# VCO_eagle.net
KiCad netlist of a schematic drawn in EAGLE
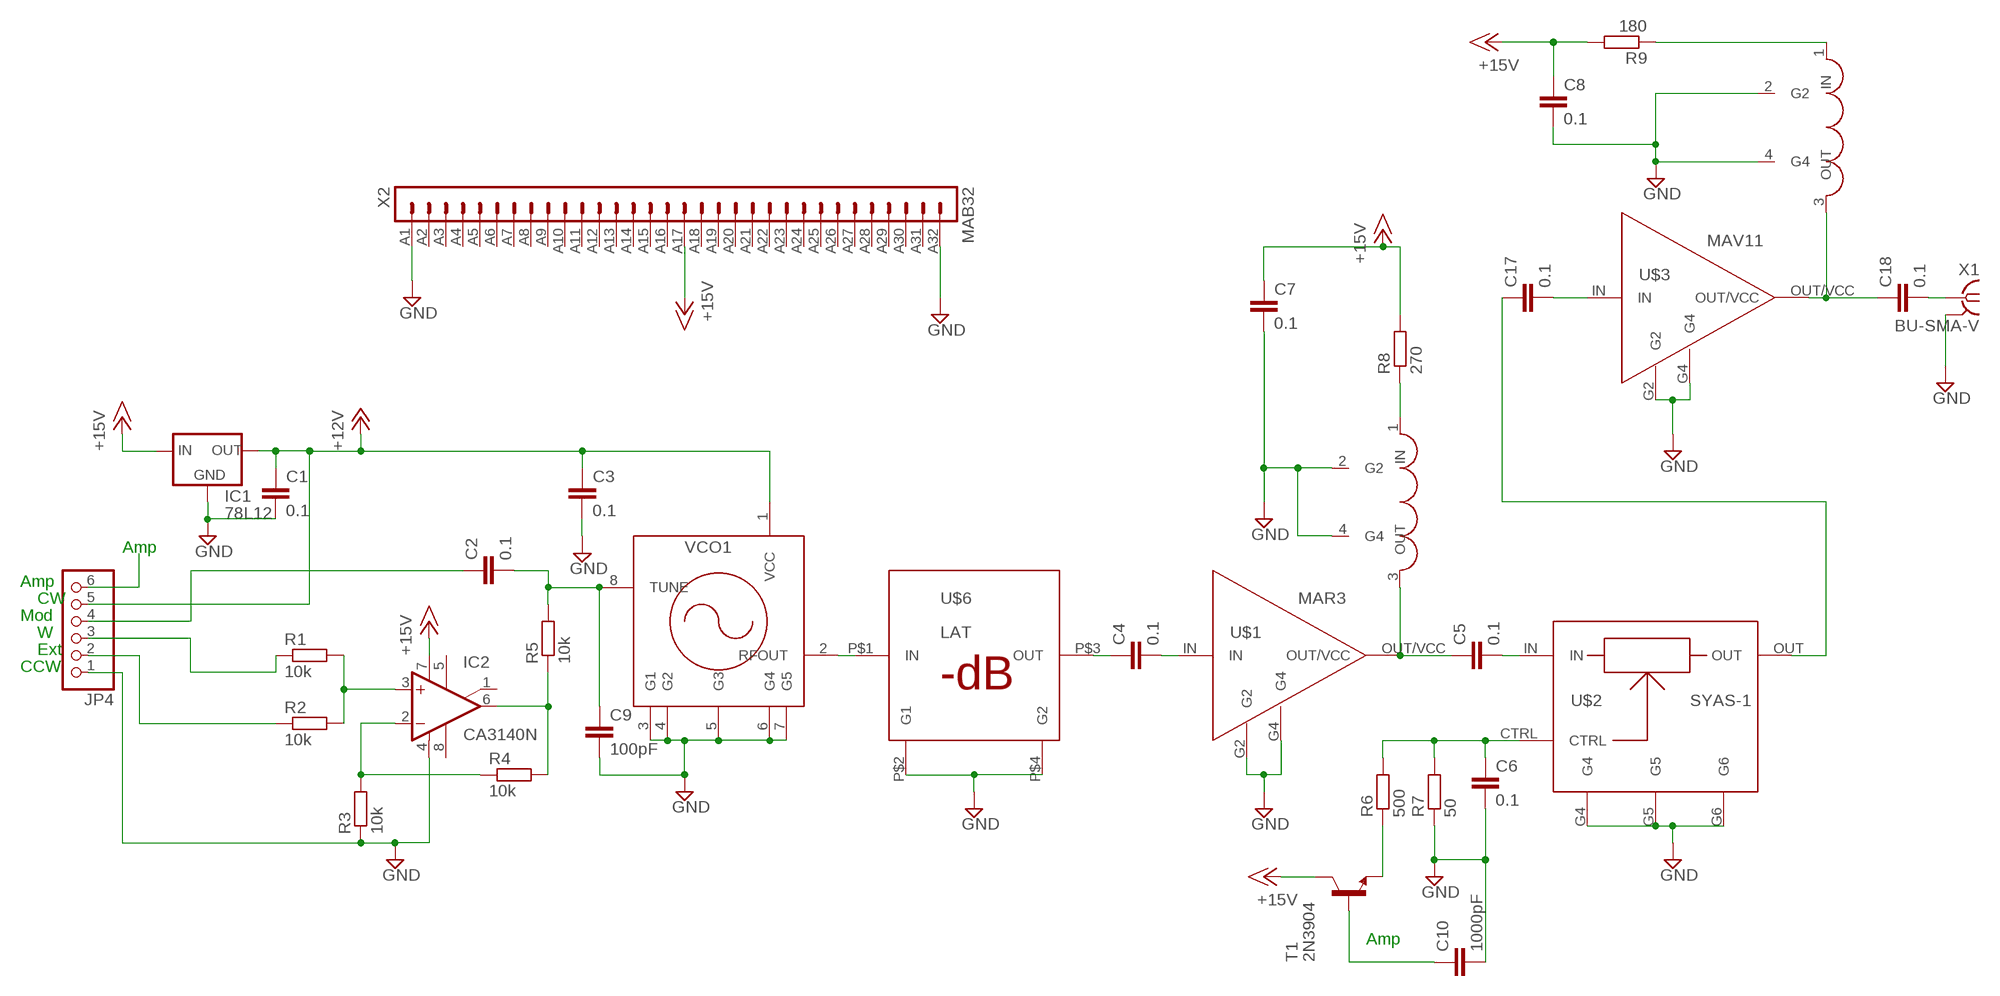
[diagram p0: schematic, sheet 1]

(export (version "E")
  (design (tool "Eeschema 10.0.6"))
  (components
    (comp (ref "C1")
      (value "0.1")
      (footprint "eagle-import:C1210")
      (libsource (lib "eagle-import") (part "C-EUC1210"))
    )
    (comp (ref "C2")
      (value "0.1")
      (footprint "eagle-import:C1210")
      (libsource (lib "eagle-import") (part "C-EUC1210"))
    )
    (comp (ref "C3")
      (value "0.1")
      (footprint "eagle-import:C1210")
      (libsource (lib "eagle-import") (part "C-EUC1210"))
    )
    (comp (ref "C4")
      (value "0.1")
      (footprint "eagle-import:C1210")
      (libsource (lib "eagle-import") (part "C-EUC1210"))
    )
    (comp (ref "C5")
      (value "0.1")
      (footprint "eagle-import:C1210")
      (libsource (lib "eagle-import") (part "C-EUC1210"))
    )
    (comp (ref "C6")
      (value "0.1")
      (footprint "eagle-import:C1210")
      (libsource (lib "eagle-import") (part "C-EUC1210"))
    )
    (comp (ref "C7")
      (value "0.1")
      (footprint "eagle-import:C1210")
      (libsource (lib "eagle-import") (part "C-EUC1210"))
    )
    (comp (ref "C8")
      (value "0.1")
      (footprint "eagle-import:C1210")
      (libsource (lib "eagle-import") (part "C-EUC1210"))
    )
    (comp (ref "C9")
      (value "100pF")
      (footprint "eagle-import:C0805")
      (libsource (lib "eagle-import") (part "C-EUC0805"))
    )
    (comp (ref "C10")
      (value "1000pF")
      (footprint "eagle-import:C0805")
      (libsource (lib "eagle-import") (part "C-EUC0805"))
    )
    (comp (ref "C17")
      (value "0.1")
      (footprint "eagle-import:C1206")
      (libsource (lib "eagle-import") (part "C-EUC1206"))
    )
    (comp (ref "C18")
      (value "0.1")
      (footprint "eagle-import:C1206")
      (libsource (lib "eagle-import") (part "C-EUC1206"))
    )
    (comp (ref "IC1")
      (value "78L12")
      (footprint "eagle-import:78LXX")
      (libsource (lib "eagle-import") (part "78LXX"))
    )
    (comp (ref "IC2")
      (value "CA3140N")
      (footprint "eagle-import:DIL08")
      (libsource (lib "eagle-import") (part "CA3140N"))
    )
    (comp (ref "JP4")
      (value "PINHD-1X6")
      (footprint "eagle-import:1X06")
      (libsource (lib "eagle-import") (part "PINHD-1X6"))
    )
    (comp (ref "R1")
      (value "10k")
      (footprint "eagle-import:0204_7")
      (libsource (lib "eagle-import") (part "R-EU_0204/7"))
    )
    (comp (ref "R2")
      (value "10k")
      (footprint "eagle-import:0204_7")
      (libsource (lib "eagle-import") (part "R-EU_0204/7"))
    )
    (comp (ref "R3")
      (value "10k")
      (footprint "eagle-import:0204_7")
      (libsource (lib "eagle-import") (part "R-EU_0204/7"))
    )
    (comp (ref "R4")
      (value "10k")
      (footprint "eagle-import:0204_7")
      (libsource (lib "eagle-import") (part "R-EU_0204/7"))
    )
    (comp (ref "R5")
      (value "10k")
      (footprint "eagle-import:0204_7")
      (libsource (lib "eagle-import") (part "R-EU_0204/7"))
    )
    (comp (ref "R6")
      (value "500")
      (footprint "eagle-import:0204_7")
      (libsource (lib "eagle-import") (part "R-EU_0204/7"))
    )
    (comp (ref "R7")
      (value "50")
      (footprint "eagle-import:0204_7")
      (libsource (lib "eagle-import") (part "R-EU_0204/7"))
    )
    (comp (ref "R8")
      (value "270")
      (footprint "eagle-import:R1206")
      (libsource (lib "eagle-import") (part "R-EU_R1206"))
    )
    (comp (ref "R9")
      (value "180")
      (footprint "eagle-import:R1206")
      (libsource (lib "eagle-import") (part "R-EU_R1206"))
    )
    (comp (ref "T1")
      (value "2N3904")
      (footprint "eagle-import:TO92")
      (libsource (lib "eagle-import") (part "2N3904"))
    )
    (comp (ref "U$1")
      (value "MAR3")
      (footprint "eagle-import:MAR")
      (libsource (lib "eagle-import") (part "MAR3"))
    )
    (comp (ref "U$2")
      (value "SYAS-1")
      (footprint "eagle-import:TTT166")
      (libsource (lib "eagle-import") (part "SYAS-1"))
    )
    (comp (ref "U$3")
      (value "MAV11")
      (footprint "eagle-import:MAR")
      (libsource (lib "eagle-import") (part "MAV11"))
    )
    (comp (ref "U$4")
      (value "TCCH-80")
      (footprint "eagle-import:PL-147")
      (libsource (lib "eagle-import") (part "TCCH-80"))
    )
    (comp (ref "U$5")
      (value "TCCH-80")
      (footprint "eagle-import:PL-147")
      (libsource (lib "eagle-import") (part "TCCH-80"))
    )
    (comp (ref "U$6")
      (value "LAT")
      (footprint "eagle-import:MMM168")
      (libsource (lib "eagle-import") (part "LAT"))
    )
    (comp (ref "VCO1")
      (value "POS")
      (footprint "eagle-import:A01")
      (libsource (lib "eagle-import") (part "POS"))
    )
    (comp (ref "X1")
      (value "BU-SMA-V")
      (footprint "eagle-import:BU-SMA-V")
      (libsource (lib "eagle-import") (part "BU-SMA-V"))
    )
    (comp (ref "X2")
      (value "MAB32")
      (footprint "eagle-import:MAB32")
      (libsource (lib "eagle-import") (part "MAB32"))
    )
  )
  (nets
    (net (code "1") (name "+12V") (class "Default")
      (node (ref "C1") (pin "1") (pinfunction "1_1") (pintype "passive"))
      (node (ref "C3") (pin "1") (pinfunction "1_1") (pintype "passive"))
      (node (ref "IC1") (pin "OUT") (pinfunction "OUT_OUT") (pintype "passive"))
      (node (ref "JP4") (pin "5") (pinfunction "5_5") (pintype "passive"))
      (node (ref "VCO1") (pin "1") (pinfunction "VCC_1") (pintype "input"))
    )
    (net (code "2") (name "+15V") (class "Default")
      (node (ref "C7") (pin "1") (pinfunction "1_1") (pintype "passive"))
      (node (ref "C8") (pin "1") (pinfunction "1_1") (pintype "passive"))
      (node (ref "IC1") (pin "IN") (pinfunction "IN_IN") (pintype "input"))
      (node (ref "IC2") (pin "7") (pinfunction "V+_7") (pintype "power_in"))
      (node (ref "R8") (pin "2") (pinfunction "2_2") (pintype "passive"))
      (node (ref "R9") (pin "2") (pinfunction "2_2") (pintype "passive"))
      (node (ref "T1") (pin "1") (pinfunction "C_1") (pintype "passive"))
      (node (ref "X2") (pin "A17") (pinfunction "17_A17") (pintype "passive"))
    )
    (net (code "3") (name "/AMP") (class "Default")
      (node (ref "C10") (pin "1") (pinfunction "1_1") (pintype "passive"))
      (node (ref "JP4") (pin "6") (pinfunction "6_6") (pintype "passive"))
      (node (ref "T1") (pin "2") (pinfunction "B_2") (pintype "passive"))
    )
    (net (code "4") (name "GND") (class "Default")
      (node (ref "C1") (pin "2") (pinfunction "2_2") (pintype "passive"))
      (node (ref "C10") (pin "2") (pinfunction "2_2") (pintype "passive"))
      (node (ref "C3") (pin "2") (pinfunction "2_2") (pintype "passive"))
      (node (ref "C6") (pin "2") (pinfunction "2_2") (pintype "passive"))
      (node (ref "C7") (pin "2") (pinfunction "2_2") (pintype "passive"))
      (node (ref "C8") (pin "2") (pinfunction "2_2") (pintype "passive"))
      (node (ref "C9") (pin "2") (pinfunction "2_2") (pintype "passive"))
      (node (ref "IC1") (pin "GND") (pinfunction "GND_GND") (pintype "input"))
      (node (ref "IC2") (pin "4") (pinfunction "V-_4") (pintype "power_in"))
      (node (ref "JP4") (pin "1") (pinfunction "1_1") (pintype "passive"))
      (node (ref "R3") (pin "1") (pinfunction "1_1") (pintype "passive"))
      (node (ref "R7") (pin "1") (pinfunction "1_1") (pintype "passive"))
      (node (ref "U$1") (pin "G2") (pinfunction "G2_G2") (pintype "power_in"))
      (node (ref "U$1") (pin "G4") (pinfunction "G4_G4") (pintype "power_in"))
      (node (ref "U$2") (pin "G4") (pinfunction "G4_G4") (pintype "power_in"))
      (node (ref "U$2") (pin "G5") (pinfunction "G5_G5") (pintype "power_in"))
      (node (ref "U$2") (pin "G6") (pinfunction "G6_G6") (pintype "power_in"))
      (node (ref "U$3") (pin "G2") (pinfunction "G2_G2") (pintype "power_in"))
      (node (ref "U$3") (pin "G4") (pinfunction "G4_G4") (pintype "power_in"))
      (node (ref "U$4") (pin "2") (pinfunction "G2_2") (pintype "power_in"))
      (node (ref "U$4") (pin "4") (pinfunction "G4_4") (pintype "power_in"))
      (node (ref "U$5") (pin "2") (pinfunction "G2_2") (pintype "power_in"))
      (node (ref "U$5") (pin "4") (pinfunction "G4_4") (pintype "power_in"))
      (node (ref "U$6") (pin "P$2") (pinfunction "G1_P$2") (pintype "power_in"))
      (node (ref "U$6") (pin "P$4") (pinfunction "G2_P$4") (pintype "power_in"))
      (node (ref "VCO1") (pin "3") (pinfunction "G1_3") (pintype "power_in"))
      (node (ref "VCO1") (pin "4") (pinfunction "G2_4") (pintype "power_in"))
      (node (ref "VCO1") (pin "5") (pinfunction "G3_5") (pintype "power_in"))
      (node (ref "VCO1") (pin "6") (pinfunction "G4_6") (pintype "power_in"))
      (node (ref "VCO1") (pin "7") (pinfunction "G5_7") (pintype "power_in"))
      (node (ref "X1") (pin "2") (pinfunction "GND_2") (pintype "power_in"))
      (node (ref "X2") (pin "A1") (pinfunction "1_A1") (pintype "passive"))
      (node (ref "X2") (pin "A32") (pinfunction "32_A32") (pintype "passive"))
    )
    (net (code "5") (name "Net-(C2-Pad1)") (class "Default")
      (node (ref "C2") (pin "1") (pinfunction "1_1") (pintype "passive"))
      (node (ref "JP4") (pin "4") (pinfunction "4_4") (pintype "passive"))
    )
    (net (code "6") (name "Net-(C4-Pad2)") (class "Default")
      (node (ref "C4") (pin "2") (pinfunction "2_2") (pintype "passive"))
      (node (ref "U$1") (pin "IN") (pinfunction "IN_IN") (pintype "input"))
    )
    (net (code "7") (name "Net-(C5-Pad2)") (class "Default")
      (node (ref "C5") (pin "2") (pinfunction "2_2") (pintype "passive"))
      (node (ref "U$2") (pin "IN") (pinfunction "IN_IN") (pintype "input"))
    )
    (net (code "8") (name "Net-(C6-Pad1)") (class "Default")
      (node (ref "C6") (pin "1") (pinfunction "1_1") (pintype "passive"))
      (node (ref "R6") (pin "2") (pinfunction "2_2") (pintype "passive"))
      (node (ref "R7") (pin "2") (pinfunction "2_2") (pintype "passive"))
      (node (ref "U$2") (pin "CTRL") (pinfunction "CTRL_CTRL") (pintype "input"))
    )
    (net (code "9") (name "Net-(C17-Pad1)") (class "Default")
      (node (ref "C17") (pin "1") (pinfunction "1_1") (pintype "passive"))
      (node (ref "U$2") (pin "OUT") (pinfunction "OUT_OUT") (pintype "output"))
    )
    (net (code "10") (name "Net-(C17-Pad2)") (class "Default")
      (node (ref "C17") (pin "2") (pinfunction "2_2") (pintype "passive"))
      (node (ref "U$3") (pin "IN") (pinfunction "IN_IN") (pintype "input"))
    )
    (net (code "11") (name "Net-(C18-Pad2)") (class "Default")
      (node (ref "C18") (pin "2") (pinfunction "2_2") (pintype "passive"))
      (node (ref "X1") (pin "1") (pinfunction "1_1") (pintype "passive"))
    )
    (net (code "12") (name "Net-(IC2-+IN)") (class "Default")
      (node (ref "IC2") (pin "3") (pinfunction "+IN_3") (pintype "input"))
      (node (ref "R1") (pin "2") (pinfunction "2_2") (pintype "passive"))
      (node (ref "R2") (pin "2") (pinfunction "2_2") (pintype "passive"))
    )
    (net (code "13") (name "Net-(IC2--IN)") (class "Default")
      (node (ref "IC2") (pin "2") (pinfunction "-IN_2") (pintype "input"))
      (node (ref "R3") (pin "2") (pinfunction "2_2") (pintype "passive"))
      (node (ref "R4") (pin "1") (pinfunction "1_1") (pintype "passive"))
    )
    (net (code "14") (name "Net-(IC2-OUT)") (class "Default")
      (node (ref "IC2") (pin "6") (pinfunction "OUT_6") (pintype "output"))
      (node (ref "R4") (pin "2") (pinfunction "2_2") (pintype "passive"))
      (node (ref "R5") (pin "1") (pinfunction "1_1") (pintype "passive"))
    )
    (net (code "15") (name "Net-(JP4-Pad2)") (class "Default")
      (node (ref "JP4") (pin "2") (pinfunction "2_2") (pintype "passive"))
      (node (ref "R2") (pin "1") (pinfunction "1_1") (pintype "passive"))
    )
    (net (code "16") (name "Net-(JP4-Pad3)") (class "Default")
      (node (ref "JP4") (pin "3") (pinfunction "3_3") (pintype "passive"))
      (node (ref "R1") (pin "1") (pinfunction "1_1") (pintype "passive"))
    )
    (net (code "17") (name "Net-(T1-E)") (class "Default")
      (node (ref "R6") (pin "1") (pinfunction "1_1") (pintype "passive"))
      (node (ref "T1") (pin "3") (pinfunction "E_3") (pintype "passive"))
    )
    (net (code "18") (name "Net-(U$4-IN)") (class "Default")
      (node (ref "R8") (pin "1") (pinfunction "1_1") (pintype "passive"))
      (node (ref "U$4") (pin "1") (pinfunction "IN_1") (pintype "input"))
    )
    (net (code "19") (name "Net-(U$4-OUT)") (class "Default")
      (node (ref "C5") (pin "1") (pinfunction "1_1") (pintype "passive"))
      (node (ref "U$1") (pin "OUT/VCC") (pinfunction "OUT/VCC_OUT/VCC") (pintype "bidirectional"))
      (node (ref "U$4") (pin "3") (pinfunction "OUT_3") (pintype "output"))
    )
    (net (code "20") (name "Net-(U$5-IN)") (class "Default")
      (node (ref "R9") (pin "1") (pinfunction "1_1") (pintype "passive"))
      (node (ref "U$5") (pin "1") (pinfunction "IN_1") (pintype "input"))
    )
    (net (code "21") (name "Net-(U$5-OUT)") (class "Default")
      (node (ref "C18") (pin "1") (pinfunction "1_1") (pintype "passive"))
      (node (ref "U$3") (pin "OUT/VCC") (pinfunction "OUT/VCC_OUT/VCC") (pintype "bidirectional"))
      (node (ref "U$5") (pin "3") (pinfunction "OUT_3") (pintype "output"))
    )
    (net (code "22") (name "Net-(U$6-IN)") (class "Default")
      (node (ref "U$6") (pin "P$1") (pinfunction "IN_P$1") (pintype "input"))
      (node (ref "VCO1") (pin "2") (pinfunction "RFOUT_2") (pintype "output"))
    )
    (net (code "23") (name "Net-(U$6-OUT)") (class "Default")
      (node (ref "C4") (pin "1") (pinfunction "1_1") (pintype "passive"))
      (node (ref "U$6") (pin "P$3") (pinfunction "OUT_P$3") (pintype "output"))
    )
    (net (code "24") (name "Net-(VCO1-TUNE)") (class "Default")
      (node (ref "C2") (pin "2") (pinfunction "2_2") (pintype "passive"))
      (node (ref "C9") (pin "1") (pinfunction "1_1") (pintype "passive"))
      (node (ref "R5") (pin "2") (pinfunction "2_2") (pintype "passive"))
      (node (ref "VCO1") (pin "8") (pinfunction "TUNE_8") (pintype "input"))
    )
    (net (code "25") (name "unconnected-(IC2-CMP-Pad8)") (class "Default")
      (node (ref "IC2") (pin "8") (pinfunction "CMP_8") (pintype "passive"))
    )
    (net (code "26") (name "unconnected-(IC2-ON-Pad5)") (class "Default")
      (node (ref "IC2") (pin "5") (pinfunction "ON_5") (pintype "passive"))
    )
    (net (code "27") (name "unconnected-(IC2-ON{slash}CMP-Pad1)") (class "Default")
      (node (ref "IC2") (pin "1") (pinfunction "ON/CMP_1") (pintype "passive"))
    )
    (net (code "28") (name "unconnected-(X2-2-PadA2)") (class "Default")
      (node (ref "X2") (pin "A2") (pinfunction "2_A2") (pintype "passive"))
    )
    (net (code "29") (name "unconnected-(X2-3-PadA3)") (class "Default")
      (node (ref "X2") (pin "A3") (pinfunction "3_A3") (pintype "passive"))
    )
    (net (code "30") (name "unconnected-(X2-4-PadA4)") (class "Default")
      (node (ref "X2") (pin "A4") (pinfunction "4_A4") (pintype "passive"))
    )
    (net (code "31") (name "unconnected-(X2-5-PadA5)") (class "Default")
      (node (ref "X2") (pin "A5") (pinfunction "5_A5") (pintype "passive"))
    )
    (net (code "32") (name "unconnected-(X2-6-PadA6)") (class "Default")
      (node (ref "X2") (pin "A6") (pinfunction "6_A6") (pintype "passive"))
    )
    (net (code "33") (name "unconnected-(X2-7-PadA7)") (class "Default")
      (node (ref "X2") (pin "A7") (pinfunction "7_A7") (pintype "passive"))
    )
    (net (code "34") (name "unconnected-(X2-8-PadA8)") (class "Default")
      (node (ref "X2") (pin "A8") (pinfunction "8_A8") (pintype "passive"))
    )
    (net (code "35") (name "unconnected-(X2-9-PadA9)") (class "Default")
      (node (ref "X2") (pin "A9") (pinfunction "9_A9") (pintype "passive"))
    )
    (net (code "36") (name "unconnected-(X2-10-PadA10)") (class "Default")
      (node (ref "X2") (pin "A10") (pinfunction "10_A10") (pintype "passive"))
    )
    (net (code "37") (name "unconnected-(X2-11-PadA11)") (class "Default")
      (node (ref "X2") (pin "A11") (pinfunction "11_A11") (pintype "passive"))
    )
    (net (code "38") (name "unconnected-(X2-12-PadA12)") (class "Default")
      (node (ref "X2") (pin "A12") (pinfunction "12_A12") (pintype "passive"))
    )
    (net (code "39") (name "unconnected-(X2-13-PadA13)") (class "Default")
      (node (ref "X2") (pin "A13") (pinfunction "13_A13") (pintype "passive"))
    )
    (net (code "40") (name "unconnected-(X2-14-PadA14)") (class "Default")
      (node (ref "X2") (pin "A14") (pinfunction "14_A14") (pintype "passive"))
    )
    (net (code "41") (name "unconnected-(X2-15-PadA15)") (class "Default")
      (node (ref "X2") (pin "A15") (pinfunction "15_A15") (pintype "passive"))
    )
    (net (code "42") (name "unconnected-(X2-16-PadA16)") (class "Default")
      (node (ref "X2") (pin "A16") (pinfunction "16_A16") (pintype "passive"))
    )
    (net (code "43") (name "unconnected-(X2-18-PadA18)") (class "Default")
      (node (ref "X2") (pin "A18") (pinfunction "18_A18") (pintype "passive"))
    )
    (net (code "44") (name "unconnected-(X2-19-PadA19)") (class "Default")
      (node (ref "X2") (pin "A19") (pinfunction "19_A19") (pintype "passive"))
    )
    (net (code "45") (name "unconnected-(X2-20-PadA20)") (class "Default")
      (node (ref "X2") (pin "A20") (pinfunction "20_A20") (pintype "passive"))
    )
    (net (code "46") (name "unconnected-(X2-21-PadA21)") (class "Default")
      (node (ref "X2") (pin "A21") (pinfunction "21_A21") (pintype "passive"))
    )
    (net (code "47") (name "unconnected-(X2-22-PadA22)") (class "Default")
      (node (ref "X2") (pin "A22") (pinfunction "22_A22") (pintype "passive"))
    )
    (net (code "48") (name "unconnected-(X2-23-PadA23)") (class "Default")
      (node (ref "X2") (pin "A23") (pinfunction "23_A23") (pintype "passive"))
    )
    (net (code "49") (name "unconnected-(X2-24-PadA24)") (class "Default")
      (node (ref "X2") (pin "A24") (pinfunction "24_A24") (pintype "passive"))
    )
    (net (code "50") (name "unconnected-(X2-25-PadA25)") (class "Default")
      (node (ref "X2") (pin "A25") (pinfunction "25_A25") (pintype "passive"))
    )
    (net (code "51") (name "unconnected-(X2-26-PadA26)") (class "Default")
      (node (ref "X2") (pin "A26") (pinfunction "26_A26") (pintype "passive"))
    )
    (net (code "52") (name "unconnected-(X2-27-PadA27)") (class "Default")
      (node (ref "X2") (pin "A27") (pinfunction "27_A27") (pintype "passive"))
    )
    (net (code "53") (name "unconnected-(X2-28-PadA28)") (class "Default")
      (node (ref "X2") (pin "A28") (pinfunction "28_A28") (pintype "passive"))
    )
    (net (code "54") (name "unconnected-(X2-29-PadA29)") (class "Default")
      (node (ref "X2") (pin "A29") (pinfunction "29_A29") (pintype "passive"))
    )
    (net (code "55") (name "unconnected-(X2-30-PadA30)") (class "Default")
      (node (ref "X2") (pin "A30") (pinfunction "30_A30") (pintype "passive"))
    )
    (net (code "56") (name "unconnected-(X2-31-PadA31)") (class "Default")
      (node (ref "X2") (pin "A31") (pinfunction "31_A31") (pintype "passive"))
    )
  )
)
